# JTAG_MCU.net
KiCad netlist of a schematic drawn in Altium Designer
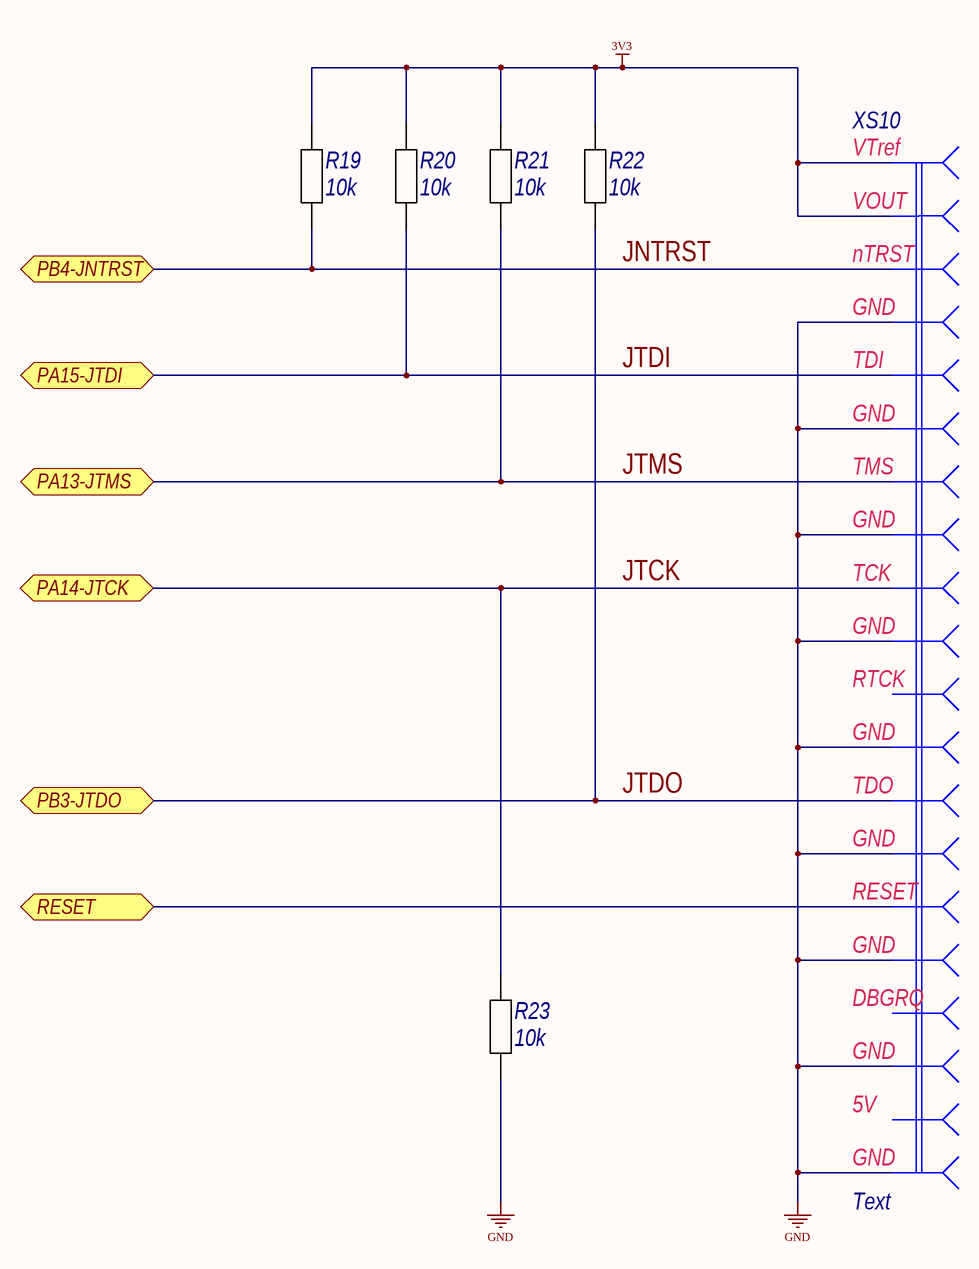
[diagram p0: JTAG_MCU.SchDoc]

(export (version "E")
  (design (tool "Eeschema 10.0.6"))
  (components
    (comp (ref "R19")
      (value "10k")
      (footprint "C0805R")
      (fields (field (name "PUBLISHER") "Andrew Danich"))
      (libsource (lib "PA_control_board") (part "R0805"))
    )
    (comp (ref "R20")
      (value "10k")
      (footprint "C0805R")
      (fields (field (name "PUBLISHER") "Andrew Danich"))
      (libsource (lib "PA_control_board") (part "R0805"))
    )
    (comp (ref "R21")
      (value "10k")
      (footprint "C0805R")
      (fields (field (name "PUBLISHER") "Andrew Danich"))
      (libsource (lib "PA_control_board") (part "R0805"))
    )
    (comp (ref "R22")
      (value "10k")
      (footprint "C0805R")
      (fields (field (name "PUBLISHER") "Andrew Danich"))
      (libsource (lib "PA_control_board") (part "R0805"))
    )
    (comp (ref "R23")
      (value "10k")
      (footprint "C0805R")
      (fields (field (name "PUBLISHER") "Andrew Danich"))
      (libsource (lib "PA_control_board") (part "R0805"))
    )
    (comp (ref "XS10")
      (value "Text")
      (footprint "IDC-20")
      (fields (field (name "PUBLISHER") "Andrew Danich"))
      (libsource (lib "PA_control_board") (part "JTAG"))
    )
  )
  (nets
    (net (code "2") (name "/JNTRST") (class "Default")
      (node (ref "R19") (pin "1") (pinfunction "1_1") (pintype "passive"))
      (node (ref "XS10") (pin "3") (pintype "passive"))
    )
    (net (code "3") (name "/JTCK") (class "Default")
      (node (ref "R23") (pin "2") (pinfunction "2_2") (pintype "passive"))
      (node (ref "XS10") (pin "9") (pintype "passive"))
    )
    (net (code "4") (name "/JTDI") (class "Default")
      (node (ref "R20") (pin "1") (pinfunction "1_1") (pintype "passive"))
      (node (ref "XS10") (pin "5") (pintype "passive"))
    )
    (net (code "5") (name "/JTDO") (class "Default")
      (node (ref "R22") (pin "1") (pinfunction "1_1") (pintype "passive"))
      (node (ref "XS10") (pin "13") (pintype "passive"))
    )
    (net (code "6") (name "/JTMS") (class "Default")
      (node (ref "R21") (pin "1") (pinfunction "1_1") (pintype "passive"))
      (node (ref "XS10") (pin "7") (pintype "passive"))
    )
    (net (code "7") (name "/RESET") (class "Default") (node (ref "XS10") (pin "15") (pintype "passive")))
    (net (code "8") (name "3V3") (class "Default")
      (node (ref "R19") (pin "2") (pinfunction "2_2") (pintype "passive"))
      (node (ref "R20") (pin "2") (pinfunction "2_2") (pintype "passive"))
      (node (ref "R21") (pin "2") (pinfunction "2_2") (pintype "passive"))
      (node (ref "R22") (pin "2") (pinfunction "2_2") (pintype "passive"))
      (node (ref "XS10") (pin "1") (pintype "passive"))
      (node (ref "XS10") (pin "2") (pintype "passive"))
    )
    (net (code "9") (name "GND") (class "Default")
      (node (ref "R23") (pin "1") (pinfunction "1_1") (pintype "passive"))
      (node (ref "XS10") (pin "10") (pintype "passive"))
      (node (ref "XS10") (pin "12") (pintype "passive"))
      (node (ref "XS10") (pin "14") (pintype "passive"))
      (node (ref "XS10") (pin "16") (pintype "passive"))
      (node (ref "XS10") (pin "18") (pintype "passive"))
      (node (ref "XS10") (pin "20") (pintype "passive"))
      (node (ref "XS10") (pin "4") (pintype "passive"))
      (node (ref "XS10") (pin "6") (pintype "passive"))
      (node (ref "XS10") (pin "8") (pintype "passive"))
    )
    (net (code "10") (name "unconnected-(XS10-Pad11)") (class "Default")
      (node (ref "XS10") (pin "11") (pintype "passive"))
    )
    (net (code "11") (name "unconnected-(XS10-Pad17)") (class "Default")
      (node (ref "XS10") (pin "17") (pintype "passive"))
    )
    (net (code "12") (name "unconnected-(XS10-Pad19)") (class "Default")
      (node (ref "XS10") (pin "19") (pintype "passive"))
    )
  )
)
